# Sheet_1_copy_2023-02-25.net
KiCad netlist of a schematic drawn in Altium Designer
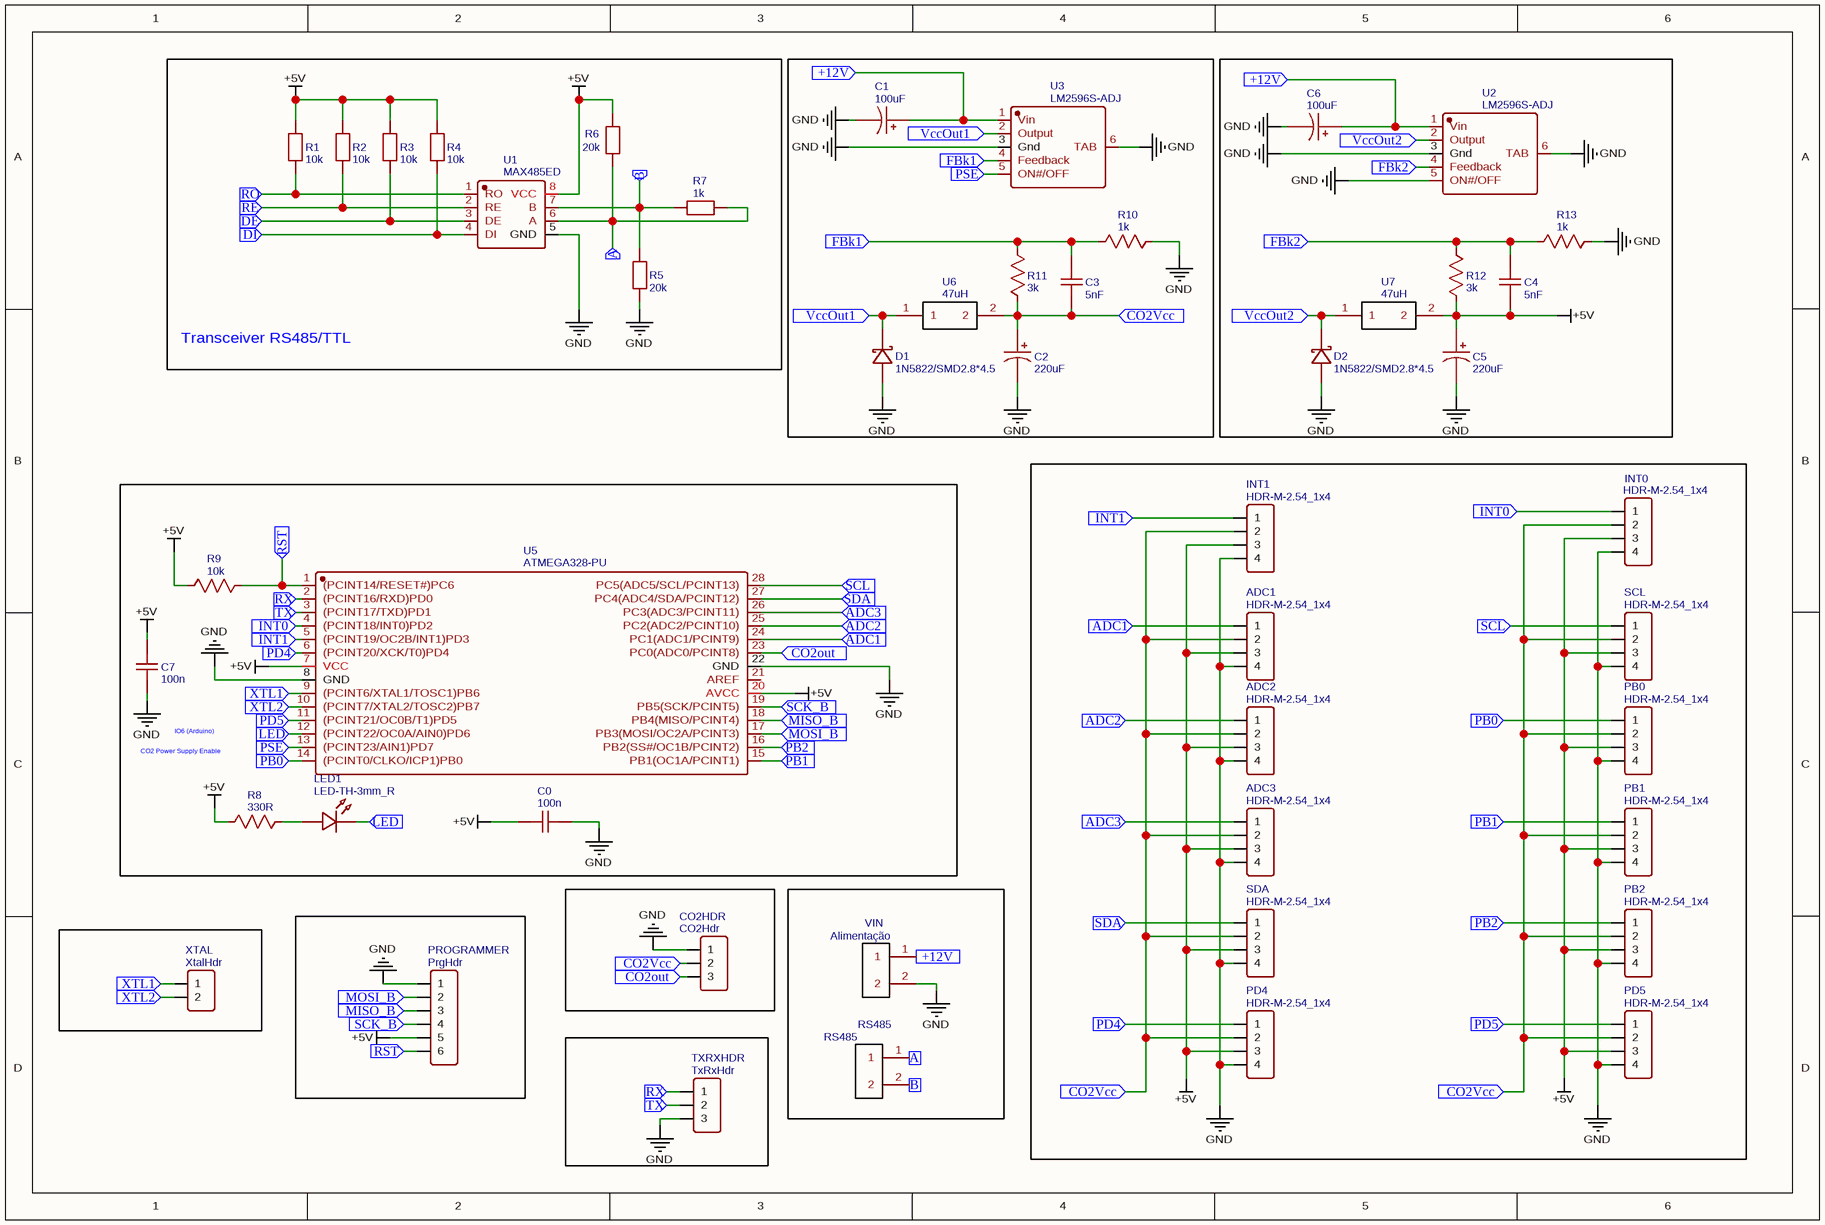
[diagram p0: Sheet_1 copy_2023-02-25.schdoc]

(export (version "E")
  (design (tool "Eeschema 10.0.6"))
  (components
    (comp (ref "ADC1")
      (value "HDR-M-2.54_1x4")
      (fields (field (name "BOM_SUPPLIER PART") "C124378") (field (name "CONTRIBUTOR") "LCEDA_Lib"))
      (libsource (lib "altium-import") (part "root_0_HDR-M-2.54_1x4_"))
    )
    (comp (ref "ADC2")
      (value "HDR-M-2.54_1x4")
      (fields (field (name "BOM_SUPPLIER PART") "C124378") (field (name "CONTRIBUTOR") "LCEDA_Lib"))
      (libsource (lib "altium-import") (part "root_0_HDR-M-2.54_1x4_"))
    )
    (comp (ref "ADC3")
      (value "HDR-M-2.54_1x4")
      (fields (field (name "BOM_SUPPLIER PART") "C124378") (field (name "CONTRIBUTOR") "LCEDA_Lib"))
      (libsource (lib "altium-import") (part "root_0_HDR-M-2.54_1x4_"))
    )
    (comp (ref "C0")
      (value "100n")
      (fields (field (name "CONTRIBUTOR") "LCEDA_Lib"))
      (libsource (lib "altium-import") (part "root_0_100n_"))
    )
    (comp (ref "C1")
      (value "100uF")
      (fields (field (name "CONTRIBUTOR") "LCEDA_Lib"))
      (libsource (lib "altium-import") (part "root_2_100uF_"))
    )
    (comp (ref "C2")
      (value "220uF")
      (fields (field (name "CONTRIBUTOR") "LCEDA_Lib"))
      (libsource (lib "altium-import") (part "root_3_220uF_"))
    )
    (comp (ref "C3")
      (value "5nF")
      (fields (field (name "CONTRIBUTOR") "LCEDA_Lib"))
      (libsource (lib "altium-import") (part "root_1_5nF_"))
    )
    (comp (ref "C4")
      (value "5nF")
      (fields (field (name "CONTRIBUTOR") "LCEDA_Lib"))
      (libsource (lib "altium-import") (part "root_1_5nF_"))
    )
    (comp (ref "C5")
      (value "220uF")
      (fields (field (name "CONTRIBUTOR") "LCEDA_Lib"))
      (libsource (lib "altium-import") (part "root_3_220uF_"))
    )
    (comp (ref "C6")
      (value "100uF")
      (fields (field (name "CONTRIBUTOR") "LCEDA_Lib"))
      (libsource (lib "altium-import") (part "root_2_100uF_"))
    )
    (comp (ref "C7")
      (value "100n")
      (fields (field (name "CONTRIBUTOR") "LCEDA_Lib"))
      (libsource (lib "altium-import") (part "root_1_100n_"))
    )
    (comp (ref "CO2HDR")
      (value "CO2Hdr")
      (fields (field (name "BOM_SUPPLIER PART") "C146690") (field (name "CONTRIBUTOR") "LCEDA_Lib"))
      (libsource (lib "altium-import") (part "root_0_CO2Hdr_"))
    )
    (comp (ref "D1")
      (value "1N5822/SMD2.8*4.5")
      (fields (field (name "BOM_SUPPLIER PART") "C9900015672") (field (name "CONTRIBUTOR") "lcsc"))
      (libsource (lib "altium-import") (part "root_3_1N5822/SMD2.8*4.5_"))
    )
    (comp (ref "D2")
      (value "1N5822/SMD2.8*4.5")
      (fields (field (name "BOM_SUPPLIER PART") "C9900015672") (field (name "CONTRIBUTOR") "lcsc"))
      (libsource (lib "altium-import") (part "root_3_1N5822/SMD2.8*4.5_"))
    )
    (comp (ref "INT0")
      (value "HDR-M-2.54_1x4")
      (fields (field (name "BOM_SUPPLIER PART") "C124378") (field (name "CONTRIBUTOR") "LCEDA_Lib"))
      (libsource (lib "altium-import") (part "root_0_HDR-M-2.54_1x4_"))
    )
    (comp (ref "INT1")
      (value "HDR-M-2.54_1x4")
      (fields (field (name "BOM_SUPPLIER PART") "C124378") (field (name "CONTRIBUTOR") "LCEDA_Lib"))
      (libsource (lib "altium-import") (part "root_0_HDR-M-2.54_1x4_"))
    )
    (comp (ref "LED1")
      (value "LED-TH-3mm_R")
      (fields
        (field (name "BOM_MANUFACTURER PART") "204-10SDRD/S530-A3-L")
        (field (name "BOM_SUPPLIER PART") "C84774")
        (field (name "CONTRIBUTOR") "LCEDA_Lib")
      )
      (libsource (lib "altium-import") (part "root_0_LED-TH-3mm_R_"))
    )
    (comp (ref "PB0")
      (value "HDR-M-2.54_1x4")
      (fields (field (name "BOM_SUPPLIER PART") "C124378") (field (name "CONTRIBUTOR") "LCEDA_Lib"))
      (libsource (lib "altium-import") (part "root_0_HDR-M-2.54_1x4_"))
    )
    (comp (ref "PB1")
      (value "HDR-M-2.54_1x4")
      (fields (field (name "BOM_SUPPLIER PART") "C124378") (field (name "CONTRIBUTOR") "LCEDA_Lib"))
      (libsource (lib "altium-import") (part "root_0_HDR-M-2.54_1x4_"))
    )
    (comp (ref "PB2")
      (value "HDR-M-2.54_1x4")
      (fields (field (name "BOM_SUPPLIER PART") "C124378") (field (name "CONTRIBUTOR") "LCEDA_Lib"))
      (libsource (lib "altium-import") (part "root_0_HDR-M-2.54_1x4_"))
    )
    (comp (ref "PD4")
      (value "HDR-M-2.54_1x4")
      (fields (field (name "BOM_SUPPLIER PART") "C124378") (field (name "CONTRIBUTOR") "LCEDA_Lib"))
      (libsource (lib "altium-import") (part "root_0_HDR-M-2.54_1x4_"))
    )
    (comp (ref "PD5")
      (value "HDR-M-2.54_1x4")
      (fields (field (name "BOM_SUPPLIER PART") "C124378") (field (name "CONTRIBUTOR") "LCEDA_Lib"))
      (libsource (lib "altium-import") (part "root_0_HDR-M-2.54_1x4_"))
    )
    (comp (ref "PROGRAMMER")
      (value "PrgHdr")
      (fields (field (name "BOM_SUPPLIER PART") "C40877") (field (name "CONTRIBUTOR") "LCEDA_Lib"))
      (libsource (lib "altium-import") (part "root_0_PrgHdr_"))
    )
    (comp (ref "R1")
      (value "10k")
      (fields (field (name "CONTRIBUTOR") "LCEDA_Lib"))
      (libsource (lib "altium-import") (part "root_1_10k_"))
    )
    (comp (ref "R2")
      (value "10k")
      (fields (field (name "CONTRIBUTOR") "LCEDA_Lib"))
      (libsource (lib "altium-import") (part "root_1_10k_"))
    )
    (comp (ref "R3")
      (value "10k")
      (fields (field (name "CONTRIBUTOR") "LCEDA_Lib"))
      (libsource (lib "altium-import") (part "root_1_10k_"))
    )
    (comp (ref "R4")
      (value "10k")
      (fields (field (name "CONTRIBUTOR") "LCEDA_Lib"))
      (libsource (lib "altium-import") (part "root_1_10k_"))
    )
    (comp (ref "R5")
      (value "20k")
      (fields (field (name "CONTRIBUTOR") "LCEDA_Lib"))
      (libsource (lib "altium-import") (part "root_1_20k_"))
    )
    (comp (ref "R6")
      (value "20k")
      (fields (field (name "CONTRIBUTOR") "LCEDA_Lib"))
      (libsource (lib "altium-import") (part "root_1_20k_"))
    )
    (comp (ref "R7")
      (value "1k")
      (fields (field (name "CONTRIBUTOR") "LCEDA_Lib"))
      (libsource (lib "altium-import") (part "root_2_1k_"))
    )
    (comp (ref "R8")
      (value "330R")
      (fields (field (name "CONTRIBUTOR") "LCEDA_Lib"))
      (libsource (lib "altium-import") (part "root_0_330R_"))
    )
    (comp (ref "R9")
      (value "10k")
      (fields (field (name "CONTRIBUTOR") "LCEDA_Lib"))
      (libsource (lib "altium-import") (part "root_0_10k_"))
    )
    (comp (ref "R10")
      (value "1k")
      (fields (field (name "CONTRIBUTOR") "LCEDA_Lib"))
      (libsource (lib "altium-import") (part "root_0_1k_"))
    )
    (comp (ref "R11")
      (value "3k")
      (fields (field (name "CONTRIBUTOR") "LCEDA_Lib"))
      (libsource (lib "altium-import") (part "root_1_3k_"))
    )
    (comp (ref "R12")
      (value "3k")
      (fields (field (name "CONTRIBUTOR") "LCEDA_Lib"))
      (libsource (lib "altium-import") (part "root_1_3k_"))
    )
    (comp (ref "R13")
      (value "1k")
      (fields (field (name "CONTRIBUTOR") "LCEDA_Lib"))
      (libsource (lib "altium-import") (part "root_0_1k_"))
    )
    (comp (ref "RS485")
      (value "RS485")
      (fields (field (name "CONTRIBUTOR") "jpcoelho1974"))
      (libsource (lib "altium-import") (part "root_0_RS485_"))
    )
    (comp (ref "SCL")
      (value "HDR-M-2.54_1x4")
      (fields (field (name "BOM_SUPPLIER PART") "C124378") (field (name "CONTRIBUTOR") "LCEDA_Lib"))
      (libsource (lib "altium-import") (part "root_0_HDR-M-2.54_1x4_"))
    )
    (comp (ref "SDA")
      (value "HDR-M-2.54_1x4")
      (fields (field (name "BOM_SUPPLIER PART") "C124378") (field (name "CONTRIBUTOR") "LCEDA_Lib"))
      (libsource (lib "altium-import") (part "root_0_HDR-M-2.54_1x4_"))
    )
    (comp (ref "TXRXHDR")
      (value "TxRxHdr")
      (fields (field (name "BOM_SUPPLIER PART") "C146690") (field (name "CONTRIBUTOR") "LCEDA_Lib"))
      (libsource (lib "altium-import") (part "root_0_TxRxHdr_"))
    )
    (comp (ref "U1")
      (value "MAX485ED")
      (fields (field (name "BOM_SUPPLIER PART") "C481667") (field (name "CONTRIBUTOR") "LCSC"))
      (libsource (lib "altium-import") (part "root_0_MAX485ED_"))
    )
    (comp (ref "U2")
      (value "LM2596S-ADJ")
      (fields (field (name "BOM_SUPPLIER PART") "C347423") (field (name "CONTRIBUTOR") "LCSC"))
      (libsource (lib "altium-import") (part "root_0_LM2596S-ADJ_"))
    )
    (comp (ref "U3")
      (value "LM2596S-ADJ")
      (fields (field (name "BOM_SUPPLIER PART") "C347423") (field (name "CONTRIBUTOR") "LCSC"))
      (libsource (lib "altium-import") (part "root_0_LM2596S-ADJ_"))
    )
    (comp (ref "U5")
      (value "ATMEGA328-PU")
      (fields (field (name "BOM_SUPPLIER PART") "C613508") (field (name "CONTRIBUTOR") "LCSC"))
      (libsource (lib "altium-import") (part "root_0_ATMEGA328-PU_"))
    )
    (comp (ref "U6")
      (value "47uH")
      (fields (field (name "CONTRIBUTOR") "jpcoelho1974"))
      (libsource (lib "altium-import") (part "root_0_47uH_"))
    )
    (comp (ref "U7")
      (value "47uH")
      (fields (field (name "CONTRIBUTOR") "jpcoelho1974"))
      (libsource (lib "altium-import") (part "root_0_47uH_"))
    )
    (comp (ref "VIN")
      (value "Alimentação")
      (fields (field (name "CONTRIBUTOR") "jpcoelho1974"))
      (libsource (lib "altium-import") (part "root_0_Alimenta玢o_"))
    )
    (comp (ref "XTAL")
      (value "XtalHdr")
      (fields (field (name "BOM_SUPPLIER PART") "C49661") (field (name "CONTRIBUTOR") "LCEDA_Lib"))
      (libsource (lib "altium-import") (part "root_0_XtalHdr_"))
    )
  )
  (nets
    (net (code "1") (name "+5V") (class "Default")
      (node (ref "ADC1") (pin "3") (pinfunction "3_3") (pintype "passive"))
      (node (ref "ADC2") (pin "3") (pinfunction "3_3") (pintype "passive"))
      (node (ref "ADC3") (pin "3") (pinfunction "3_3") (pintype "passive"))
      (node (ref "C0") (pin "1") (pinfunction "1_1") (pintype "passive"))
      (node (ref "C4") (pin "1") (pinfunction "1_1") (pintype "passive"))
      (node (ref "C5") (pin "1") (pinfunction "1_1") (pintype "passive"))
      (node (ref "C7") (pin "2") (pinfunction "2_2") (pintype "passive"))
      (node (ref "INT0") (pin "3") (pinfunction "3_3") (pintype "passive"))
      (node (ref "INT1") (pin "3") (pinfunction "3_3") (pintype "passive"))
      (node (ref "PB0") (pin "3") (pinfunction "3_3") (pintype "passive"))
      (node (ref "PB1") (pin "3") (pinfunction "3_3") (pintype "passive"))
      (node (ref "PB2") (pin "3") (pinfunction "3_3") (pintype "passive"))
      (node (ref "PD4") (pin "3") (pinfunction "3_3") (pintype "passive"))
      (node (ref "PD5") (pin "3") (pinfunction "3_3") (pintype "passive"))
      (node (ref "PROGRAMMER") (pin "5") (pinfunction "5_5") (pintype "passive"))
      (node (ref "R1") (pin "2") (pinfunction "2_2") (pintype "passive"))
      (node (ref "R12") (pin "1") (pinfunction "1_1") (pintype "passive"))
      (node (ref "R2") (pin "2") (pinfunction "2_2") (pintype "passive"))
      (node (ref "R3") (pin "2") (pinfunction "2_2") (pintype "passive"))
      (node (ref "R4") (pin "2") (pinfunction "2_2") (pintype "passive"))
      (node (ref "R6") (pin "2") (pinfunction "2_2") (pintype "passive"))
      (node (ref "R8") (pin "1") (pinfunction "1_1") (pintype "passive"))
      (node (ref "R9") (pin "1") (pinfunction "1_1") (pintype "passive"))
      (node (ref "SCL") (pin "3") (pinfunction "3_3") (pintype "passive"))
      (node (ref "SDA") (pin "3") (pinfunction "3_3") (pintype "passive"))
      (node (ref "U1") (pin "8") (pinfunction "VCC_8") (pintype "passive"))
      (node (ref "U5") (pin "20") (pinfunction "AVCC_20") (pintype "passive"))
      (node (ref "U5") (pin "7") (pinfunction "VCC_7") (pintype "passive"))
      (node (ref "U7") (pin "2") (pinfunction "2_2") (pintype "passive"))
    )
    (net (code "2") (name "/+12V") (class "Default")
      (node (ref "C1") (pin "1") (pinfunction "1_1") (pintype "passive"))
      (node (ref "C6") (pin "1") (pinfunction "1_1") (pintype "passive"))
      (node (ref "U2") (pin "1") (pinfunction "Vin_1") (pintype "passive"))
      (node (ref "U3") (pin "1") (pinfunction "Vin_1") (pintype "passive"))
      (node (ref "VIN") (pin "1") (pinfunction "1_1") (pintype "passive"))
    )
    (net (code "3") (name "/A") (class "Default")
      (node (ref "R6") (pin "1") (pinfunction "1_1") (pintype "passive"))
      (node (ref "R7") (pin "1") (pinfunction "1_1") (pintype "passive"))
      (node (ref "RS485") (pin "1") (pinfunction "1_1") (pintype "passive"))
      (node (ref "U1") (pin "6") (pinfunction "A_6") (pintype "passive"))
    )
    (net (code "4") (name "/ADC1") (class "Default")
      (node (ref "ADC1") (pin "1") (pinfunction "1_1") (pintype "passive"))
      (node (ref "U5") (pin "24") (pinfunction "PC1(ADC1/PCINT9)_24") (pintype "passive"))
    )
    (net (code "5") (name "/ADC2") (class "Default")
      (node (ref "ADC2") (pin "1") (pinfunction "1_1") (pintype "passive"))
      (node (ref "U5") (pin "25") (pinfunction "PC2(ADC2/PCINT10)_25") (pintype "passive"))
    )
    (net (code "6") (name "/ADC3") (class "Default")
      (node (ref "ADC3") (pin "1") (pinfunction "1_1") (pintype "passive"))
      (node (ref "U5") (pin "26") (pinfunction "PC3(ADC3/PCINT11)_26") (pintype "passive"))
    )
    (net (code "7") (name "/B") (class "Default")
      (node (ref "R5") (pin "2") (pinfunction "2_2") (pintype "passive"))
      (node (ref "R7") (pin "2") (pinfunction "2_2") (pintype "passive"))
      (node (ref "RS485") (pin "2") (pinfunction "2_2") (pintype "passive"))
      (node (ref "U1") (pin "7") (pinfunction "B_7") (pintype "passive"))
    )
    (net (code "8") (name "/CO2Vcc") (class "Default")
      (node (ref "ADC1") (pin "2") (pinfunction "2_2") (pintype "passive"))
      (node (ref "ADC2") (pin "2") (pinfunction "2_2") (pintype "passive"))
      (node (ref "ADC3") (pin "2") (pinfunction "2_2") (pintype "passive"))
      (node (ref "C2") (pin "1") (pinfunction "1_1") (pintype "passive"))
      (node (ref "C3") (pin "1") (pinfunction "1_1") (pintype "passive"))
      (node (ref "CO2HDR") (pin "2") (pinfunction "2_2") (pintype "passive"))
      (node (ref "INT0") (pin "2") (pinfunction "2_2") (pintype "passive"))
      (node (ref "INT1") (pin "2") (pinfunction "2_2") (pintype "passive"))
      (node (ref "PB0") (pin "2") (pinfunction "2_2") (pintype "passive"))
      (node (ref "PB1") (pin "2") (pinfunction "2_2") (pintype "passive"))
      (node (ref "PB2") (pin "2") (pinfunction "2_2") (pintype "passive"))
      (node (ref "PD4") (pin "2") (pinfunction "2_2") (pintype "passive"))
      (node (ref "PD5") (pin "2") (pinfunction "2_2") (pintype "passive"))
      (node (ref "R11") (pin "1") (pinfunction "1_1") (pintype "passive"))
      (node (ref "SCL") (pin "2") (pinfunction "2_2") (pintype "passive"))
      (node (ref "SDA") (pin "2") (pinfunction "2_2") (pintype "passive"))
      (node (ref "U6") (pin "2") (pinfunction "2_2") (pintype "passive"))
    )
    (net (code "9") (name "/CO2out") (class "Default")
      (node (ref "CO2HDR") (pin "3") (pinfunction "3_3") (pintype "passive"))
      (node (ref "U5") (pin "23") (pinfunction "PC0(ADC0/PCINT8)_23") (pintype "passive"))
    )
    (net (code "10") (name "/DE") (class "Default")
      (node (ref "R3") (pin "1") (pinfunction "1_1") (pintype "passive"))
      (node (ref "U1") (pin "3") (pinfunction "DE_3") (pintype "passive"))
    )
    (net (code "11") (name "/DI") (class "Default")
      (node (ref "R4") (pin "1") (pinfunction "1_1") (pintype "passive"))
      (node (ref "U1") (pin "4") (pinfunction "DI_4") (pintype "passive"))
    )
    (net (code "12") (name "/FBk1") (class "Default")
      (node (ref "C3") (pin "2") (pinfunction "2_2") (pintype "passive"))
      (node (ref "R10") (pin "1") (pinfunction "1_1") (pintype "passive"))
      (node (ref "R11") (pin "2") (pinfunction "2_2") (pintype "passive"))
      (node (ref "U3") (pin "4") (pinfunction "Feedback_4") (pintype "passive"))
    )
    (net (code "13") (name "/FBk2") (class "Default")
      (node (ref "C4") (pin "2") (pinfunction "2_2") (pintype "passive"))
      (node (ref "R12") (pin "2") (pinfunction "2_2") (pintype "passive"))
      (node (ref "R13") (pin "1") (pinfunction "1_1") (pintype "passive"))
      (node (ref "U2") (pin "4") (pinfunction "Feedback_4") (pintype "passive"))
    )
    (net (code "14") (name "/INT0") (class "Default")
      (node (ref "INT0") (pin "1") (pinfunction "1_1") (pintype "passive"))
      (node (ref "U5") (pin "4") (pinfunction "(PCINT18/INT0)PD2_4") (pintype "passive"))
    )
    (net (code "15") (name "/INT1") (class "Default")
      (node (ref "INT1") (pin "1") (pinfunction "1_1") (pintype "passive"))
      (node (ref "U5") (pin "5") (pinfunction "(PCINT19/OC2B/INT1)PD3_5") (pintype "passive"))
    )
    (net (code "16") (name "/LED") (class "Default")
      (node (ref "LED1") (pin "2") (pinfunction "2_2") (pintype "passive"))
      (node (ref "U5") (pin "12") (pinfunction "(PCINT22/OC0A/AIN0)PD6_12") (pintype "passive"))
    )
    (net (code "17") (name "/MISO_B") (class "Default")
      (node (ref "PROGRAMMER") (pin "3") (pinfunction "3_3") (pintype "passive"))
      (node (ref "U5") (pin "18") (pinfunction "PB4(MISO/PCINT4)_18") (pintype "passive"))
    )
    (net (code "18") (name "/MOSI_B") (class "Default")
      (node (ref "PROGRAMMER") (pin "2") (pinfunction "2_2") (pintype "passive"))
      (node (ref "U5") (pin "17") (pinfunction "PB3(MOSI/OC2A/PCINT3)_17") (pintype "passive"))
    )
    (net (code "19") (name "/PB0") (class "Default")
      (node (ref "PB0") (pin "1") (pinfunction "1_1") (pintype "passive"))
      (node (ref "U5") (pin "14") (pinfunction "(PCINT0/CLKO/ICP1)PB0_14") (pintype "passive"))
    )
    (net (code "20") (name "/PB1") (class "Default")
      (node (ref "PB1") (pin "1") (pinfunction "1_1") (pintype "passive"))
      (node (ref "U5") (pin "15") (pinfunction "PB1(OC1A/PCINT1)_15") (pintype "passive"))
    )
    (net (code "21") (name "/PB2") (class "Default")
      (node (ref "PB2") (pin "1") (pinfunction "1_1") (pintype "passive"))
      (node (ref "U5") (pin "16") (pinfunction "PB2(SS#/OC1B/PCINT2)_16") (pintype "passive"))
    )
    (net (code "22") (name "/PD4") (class "Default")
      (node (ref "PD4") (pin "1") (pinfunction "1_1") (pintype "passive"))
      (node (ref "U5") (pin "6") (pinfunction "(PCINT20/XCK/T0)PD4_6") (pintype "passive"))
    )
    (net (code "23") (name "/PD5") (class "Default")
      (node (ref "PD5") (pin "1") (pinfunction "1_1") (pintype "passive"))
      (node (ref "U5") (pin "11") (pinfunction "(PCINT21/OC0B/T1)PD5_11") (pintype "passive"))
    )
    (net (code "24") (name "/PSE") (class "Default")
      (node (ref "U3") (pin "5") (pinfunction "ON#/OFF_5") (pintype "passive"))
      (node (ref "U5") (pin "13") (pinfunction "(PCINT23/AIN1)PD7_13") (pintype "passive"))
    )
    (net (code "25") (name "/RE") (class "Default")
      (node (ref "R2") (pin "1") (pinfunction "1_1") (pintype "passive"))
      (node (ref "U1") (pin "2") (pinfunction "RE_2") (pintype "passive"))
    )
    (net (code "26") (name "/RO") (class "Default")
      (node (ref "R1") (pin "1") (pinfunction "1_1") (pintype "passive"))
      (node (ref "U1") (pin "1") (pinfunction "RO_1") (pintype "passive"))
    )
    (net (code "27") (name "/RST") (class "Default")
      (node (ref "PROGRAMMER") (pin "6") (pinfunction "6_6") (pintype "passive"))
      (node (ref "R9") (pin "2") (pinfunction "2_2") (pintype "passive"))
      (node (ref "U5") (pin "1") (pinfunction "(PCINT14/RESET#)PC6_1") (pintype "passive"))
    )
    (net (code "28") (name "/RX") (class "Default")
      (node (ref "TXRXHDR") (pin "1") (pinfunction "1_1") (pintype "passive"))
      (node (ref "U5") (pin "2") (pinfunction "(PCINT16/RXD)PD0_2") (pintype "passive"))
    )
    (net (code "29") (name "/SCK_B") (class "Default")
      (node (ref "PROGRAMMER") (pin "4") (pinfunction "4_4") (pintype "passive"))
      (node (ref "U5") (pin "19") (pinfunction "PB5(SCK/PCINT5)_19") (pintype "passive"))
    )
    (net (code "30") (name "/SCL") (class "Default")
      (node (ref "SCL") (pin "1") (pinfunction "1_1") (pintype "passive"))
      (node (ref "U5") (pin "28") (pinfunction "PC5(ADC5/SCL/PCINT13)_28") (pintype "passive"))
    )
    (net (code "31") (name "/SDA") (class "Default")
      (node (ref "SDA") (pin "1") (pinfunction "1_1") (pintype "passive"))
      (node (ref "U5") (pin "27") (pinfunction "PC4(ADC4/SDA/PCINT12)_27") (pintype "passive"))
    )
    (net (code "32") (name "/TX") (class "Default")
      (node (ref "TXRXHDR") (pin "2") (pinfunction "2_2") (pintype "passive"))
      (node (ref "U5") (pin "3") (pinfunction "(PCINT17/TXD)PD1_3") (pintype "passive"))
    )
    (net (code "33") (name "/VccOut1") (class "Default")
      (node (ref "D1") (pin "1") (pinfunction "A_1") (pintype "passive"))
      (node (ref "U3") (pin "2") (pinfunction "Output_2") (pintype "passive"))
      (node (ref "U6") (pin "1") (pinfunction "1_1") (pintype "passive"))
    )
    (net (code "34") (name "/VccOut2") (class "Default")
      (node (ref "D2") (pin "1") (pinfunction "A_1") (pintype "passive"))
      (node (ref "U2") (pin "2") (pinfunction "Output_2") (pintype "passive"))
      (node (ref "U7") (pin "1") (pinfunction "1_1") (pintype "passive"))
    )
    (net (code "35") (name "/XTL1") (class "Default")
      (node (ref "U5") (pin "9") (pinfunction "(PCINT6/XTAL1/TOSC1)PB6_9") (pintype "passive"))
      (node (ref "XTAL") (pin "1") (pinfunction "1_1") (pintype "passive"))
    )
    (net (code "36") (name "/XTL2") (class "Default")
      (node (ref "U5") (pin "10") (pinfunction "(PCINT7/XTAL2/TOSC2)PB7_10") (pintype "passive"))
      (node (ref "XTAL") (pin "2") (pinfunction "2_2") (pintype "passive"))
    )
    (net (code "37") (name "GND") (class "Default")
      (node (ref "ADC1") (pin "4") (pinfunction "4_4") (pintype "passive"))
      (node (ref "ADC2") (pin "4") (pinfunction "4_4") (pintype "passive"))
      (node (ref "ADC3") (pin "4") (pinfunction "4_4") (pintype "passive"))
      (node (ref "C0") (pin "2") (pinfunction "2_2") (pintype "passive"))
      (node (ref "C1") (pin "2") (pinfunction "2_2") (pintype "passive"))
      (node (ref "C2") (pin "2") (pinfunction "2_2") (pintype "passive"))
      (node (ref "C5") (pin "2") (pinfunction "2_2") (pintype "passive"))
      (node (ref "C6") (pin "2") (pinfunction "2_2") (pintype "passive"))
      (node (ref "C7") (pin "1") (pinfunction "1_1") (pintype "passive"))
      (node (ref "CO2HDR") (pin "1") (pinfunction "1_1") (pintype "passive"))
      (node (ref "D1") (pin "2") (pinfunction "K_2") (pintype "passive"))
      (node (ref "D2") (pin "2") (pinfunction "K_2") (pintype "passive"))
      (node (ref "INT0") (pin "4") (pinfunction "4_4") (pintype "passive"))
      (node (ref "INT1") (pin "4") (pinfunction "4_4") (pintype "passive"))
      (node (ref "PB0") (pin "4") (pinfunction "4_4") (pintype "passive"))
      (node (ref "PB1") (pin "4") (pinfunction "4_4") (pintype "passive"))
      (node (ref "PB2") (pin "4") (pinfunction "4_4") (pintype "passive"))
      (node (ref "PD4") (pin "4") (pinfunction "4_4") (pintype "passive"))
      (node (ref "PD5") (pin "4") (pinfunction "4_4") (pintype "passive"))
      (node (ref "PROGRAMMER") (pin "1") (pinfunction "1_1") (pintype "passive"))
      (node (ref "R10") (pin "2") (pinfunction "2_2") (pintype "passive"))
      (node (ref "R13") (pin "2") (pinfunction "2_2") (pintype "passive"))
      (node (ref "R5") (pin "1") (pinfunction "1_1") (pintype "passive"))
      (node (ref "SCL") (pin "4") (pinfunction "4_4") (pintype "passive"))
      (node (ref "SDA") (pin "4") (pinfunction "4_4") (pintype "passive"))
      (node (ref "TXRXHDR") (pin "3") (pinfunction "3_3") (pintype "passive"))
      (node (ref "U1") (pin "5") (pinfunction "GND_5") (pintype "passive"))
      (node (ref "U2") (pin "3") (pinfunction "Gnd_3") (pintype "passive"))
      (node (ref "U2") (pin "5") (pinfunction "ON#/OFF_5") (pintype "passive"))
      (node (ref "U2") (pin "6") (pinfunction "TAB_6") (pintype "passive"))
      (node (ref "U3") (pin "3") (pinfunction "Gnd_3") (pintype "passive"))
      (node (ref "U3") (pin "6") (pinfunction "TAB_6") (pintype "passive"))
      (node (ref "U5") (pin "22") (pinfunction "GND_22") (pintype "passive"))
      (node (ref "U5") (pin "8") (pinfunction "GND_8") (pintype "passive"))
      (node (ref "VIN") (pin "2") (pinfunction "2_2") (pintype "passive"))
    )
    (net (code "38") (name "Net-(LED1-Pad1)") (class "Default")
      (node (ref "LED1") (pin "1") (pinfunction "1_1") (pintype "passive"))
      (node (ref "R8") (pin "2") (pinfunction "2_2") (pintype "passive"))
    )
    (net (code "39") (name "unconnected-(U5-AREF-Pad21)") (class "Default")
      (node (ref "U5") (pin "21") (pinfunction "AREF_21") (pintype "passive"))
    )
  )
)
